# io3.net
KiCad netlist of a schematic drawn in EAGLE
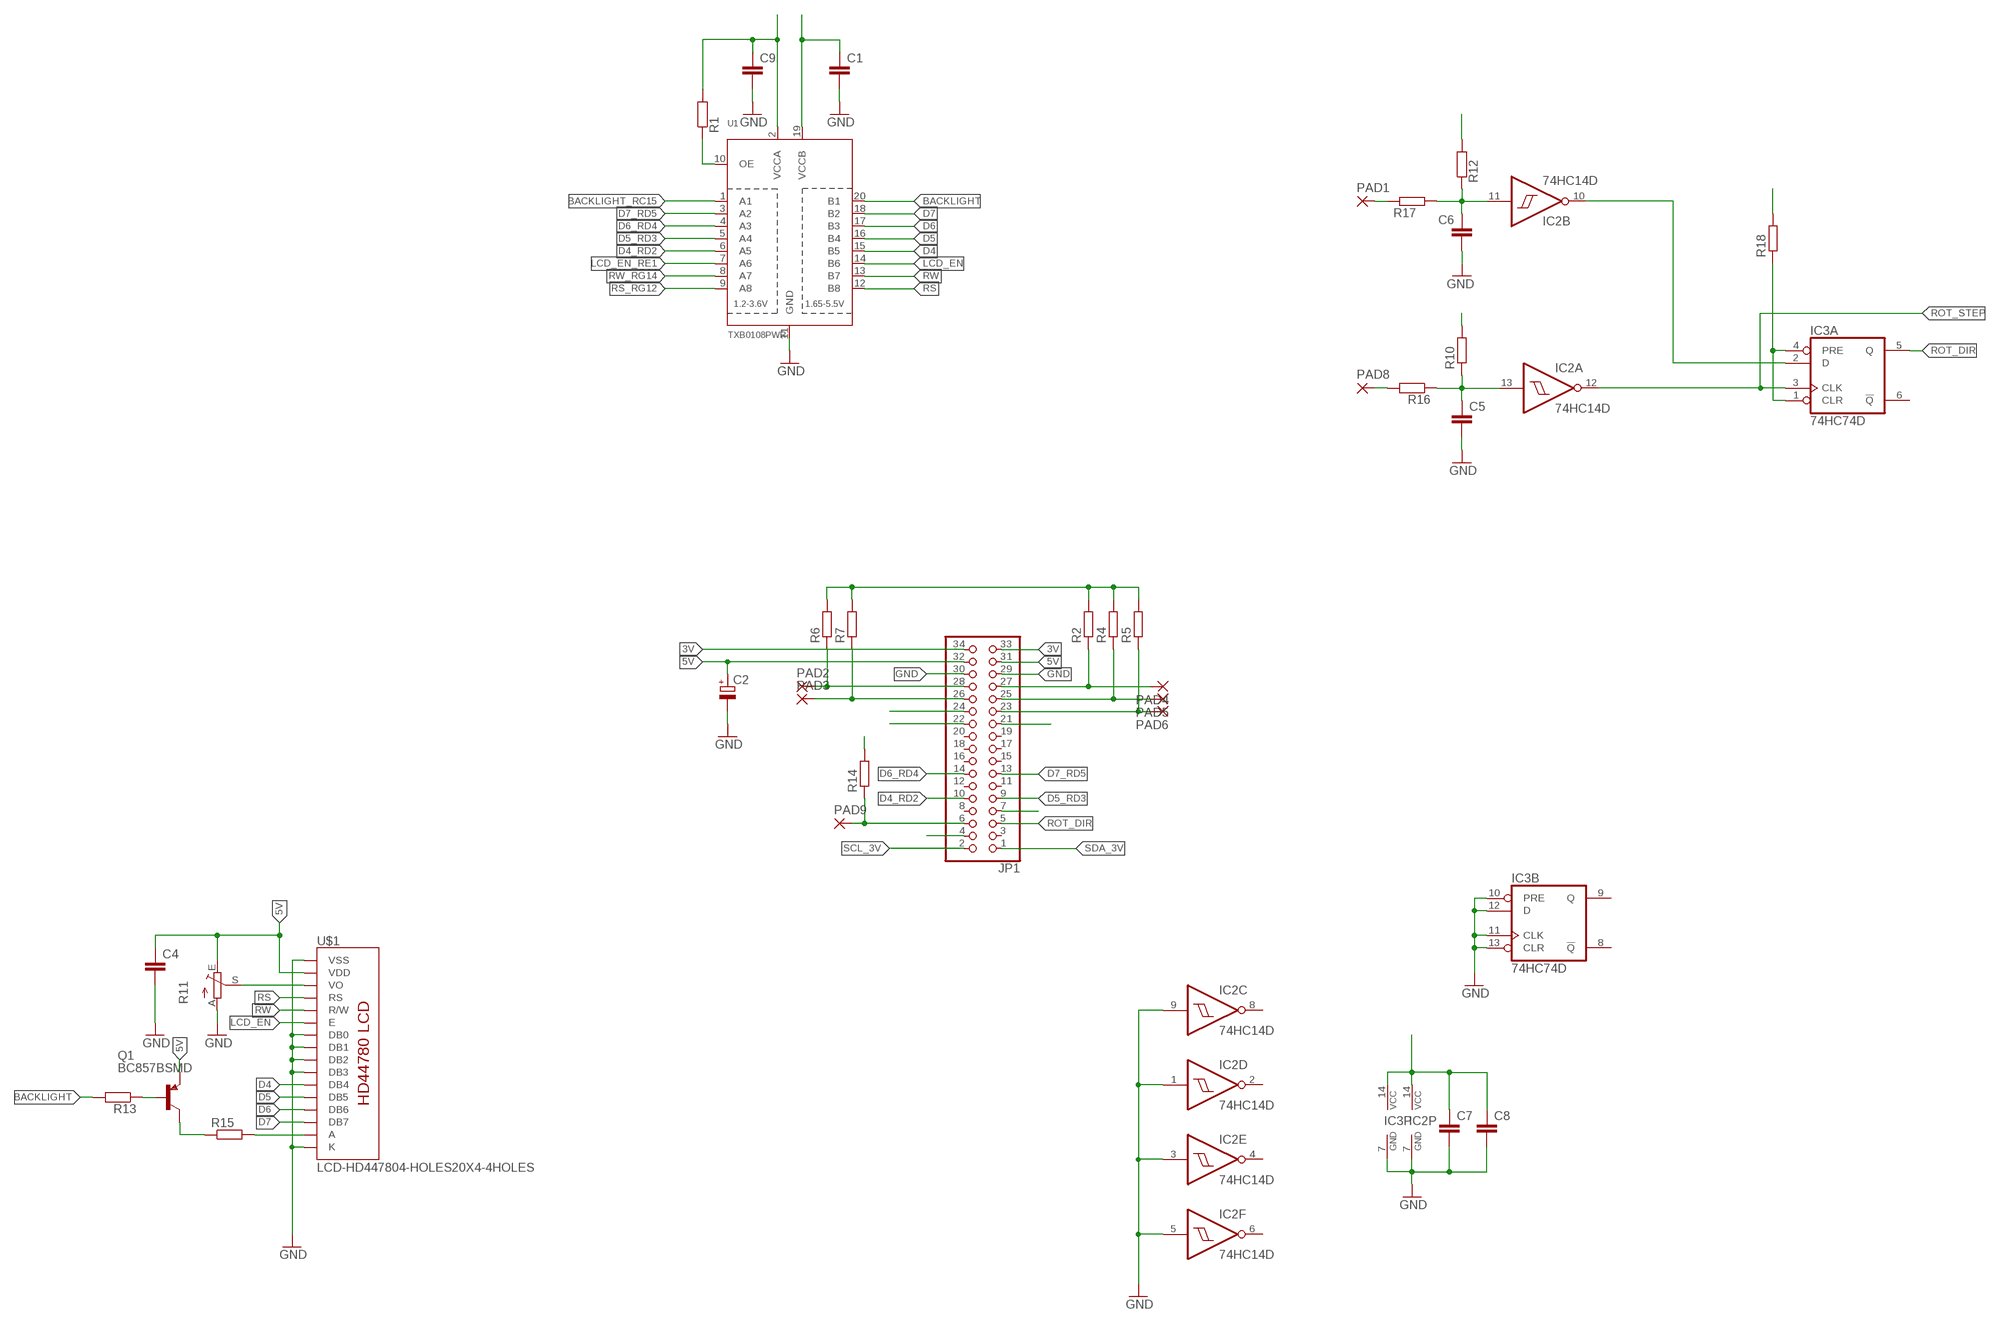
[diagram p0: schematic, sheet 1]

(export (version "E")
  (design (tool "Eeschema 10.0.6"))
  (components
    (comp (ref "C1")
      (value "C-EUC0603")
      (footprint "eagle-import:C0603")
      (libsource (lib "eagle-import") (part "C-EUC0603"))
    )
    (comp (ref "C2")
      (value "CPOL-EUSMCD")
      (footprint "eagle-import:SMC_D")
      (libsource (lib "eagle-import") (part "CPOL-EUSMCD"))
    )
    (comp (ref "C4")
      (value "C-EUC1206")
      (footprint "eagle-import:C1206")
      (libsource (lib "eagle-import") (part "C-EUC1206"))
    )
    (comp (ref "C5")
      (value "C-EUC0603")
      (footprint "eagle-import:C0603")
      (libsource (lib "eagle-import") (part "C-EUC0603"))
    )
    (comp (ref "C6")
      (value "C-EUC0603")
      (footprint "eagle-import:C0603")
      (libsource (lib "eagle-import") (part "C-EUC0603"))
    )
    (comp (ref "C7")
      (value "C-EUC0603")
      (footprint "eagle-import:C0603")
      (libsource (lib "eagle-import") (part "C-EUC0603"))
    )
    (comp (ref "C8")
      (value "C-EUC0603")
      (footprint "eagle-import:C0603")
      (libsource (lib "eagle-import") (part "C-EUC0603"))
    )
    (comp (ref "C9")
      (value "C-EUC0603")
      (footprint "eagle-import:C0603")
      (libsource (lib "eagle-import") (part "C-EUC0603"))
    )
    (comp (ref "IC2")
      (value "74HC14D")
      (footprint "eagle-import:SO14")
      (libsource (lib "eagle-import") (part "7414DHC"))
    )
    (comp (ref "IC3")
      (value "74HC74D")
      (footprint "eagle-import:SO14")
      (libsource (lib "eagle-import") (part "7474DHC"))
    )
    (comp (ref "JP1")
      (value "PINHD-2X17_2.54-SMD")
      (footprint "eagle-import:2X17SMD")
      (libsource (lib "eagle-import") (part "PINHD-2X17_2.54-SMD"))
    )
    (comp (ref "PAD1")
      (value "SMD2")
      (footprint "eagle-import:SMD1,27-2,54")
      (libsource (lib "eagle-import") (part "SMD2"))
    )
    (comp (ref "PAD2")
      (value "SMD2")
      (footprint "eagle-import:SMD1,27-2,54")
      (libsource (lib "eagle-import") (part "SMD2"))
    )
    (comp (ref "PAD3")
      (value "SMD2")
      (footprint "eagle-import:SMD1,27-2,54")
      (libsource (lib "eagle-import") (part "SMD2"))
    )
    (comp (ref "PAD4")
      (value "SMD2")
      (footprint "eagle-import:SMD1,27-2,54")
      (libsource (lib "eagle-import") (part "SMD2"))
    )
    (comp (ref "PAD5")
      (value "SMD2")
      (footprint "eagle-import:SMD1,27-2,54")
      (libsource (lib "eagle-import") (part "SMD2"))
    )
    (comp (ref "PAD6")
      (value "SMD2")
      (footprint "eagle-import:SMD1,27-2,54")
      (libsource (lib "eagle-import") (part "SMD2"))
    )
    (comp (ref "PAD8")
      (value "SMD2")
      (footprint "eagle-import:SMD1,27-2,54")
      (libsource (lib "eagle-import") (part "SMD2"))
    )
    (comp (ref "PAD9")
      (value "SMD2")
      (footprint "eagle-import:SMD1,27-2,54")
      (libsource (lib "eagle-import") (part "SMD2"))
    )
    (comp (ref "Q1")
      (value "BC857BSMD")
      (footprint "eagle-import:SOT23-BEC")
      (libsource (lib "eagle-import") (part "BC857SMDB"))
    )
    (comp (ref "R1")
      (value "R-EU_R0603")
      (footprint "eagle-import:R0603")
      (libsource (lib "eagle-import") (part "R-EU_R0603"))
    )
    (comp (ref "R2")
      (value "R-EU_0204/7")
      (footprint "eagle-import:0204_7")
      (libsource (lib "eagle-import") (part "R-EU_0204/7"))
    )
    (comp (ref "R4")
      (value "R-EU_0204/7")
      (footprint "eagle-import:0204_7")
      (libsource (lib "eagle-import") (part "R-EU_0204/7"))
    )
    (comp (ref "R5")
      (value "R-EU_0204/7")
      (footprint "eagle-import:0204_7")
      (libsource (lib "eagle-import") (part "R-EU_0204/7"))
    )
    (comp (ref "R6")
      (value "R-EU_0204/7")
      (footprint "eagle-import:0204_7")
      (libsource (lib "eagle-import") (part "R-EU_0204/7"))
    )
    (comp (ref "R7")
      (value "R-EU_0204/7")
      (footprint "eagle-import:0204_7")
      (libsource (lib "eagle-import") (part "R-EU_0204/7"))
    )
    (comp (ref "R10")
      (value "R-EU_0204/7")
      (footprint "eagle-import:0204_7")
      (libsource (lib "eagle-import") (part "R-EU_0204/7"))
    )
    (comp (ref "R11")
      (value "TRIM_EU-B25U")
      (footprint "eagle-import:B25U")
      (libsource (lib "eagle-import") (part "TRIM_EU-B25U"))
    )
    (comp (ref "R12")
      (value "R-EU_0204/7")
      (footprint "eagle-import:0204_7")
      (libsource (lib "eagle-import") (part "R-EU_0204/7"))
    )
    (comp (ref "R13")
      (value "R-EU_R0603")
      (footprint "eagle-import:R0603")
      (libsource (lib "eagle-import") (part "R-EU_R0603"))
    )
    (comp (ref "R14")
      (value "R-EU_0204/5")
      (footprint "eagle-import:0204_5")
      (libsource (lib "eagle-import") (part "R-EU_0204/5"))
    )
    (comp (ref "R15")
      (value "R-EU_R1206")
      (footprint "eagle-import:R1206")
      (libsource (lib "eagle-import") (part "R-EU_R1206"))
    )
    (comp (ref "R16")
      (value "R-EU_R0603")
      (footprint "eagle-import:R0603")
      (libsource (lib "eagle-import") (part "R-EU_R0603"))
    )
    (comp (ref "R17")
      (value "R-EU_R0603")
      (footprint "eagle-import:R0603")
      (libsource (lib "eagle-import") (part "R-EU_R0603"))
    )
    (comp (ref "R18")
      (value "R-EU_0204/7")
      (footprint "eagle-import:0204_7")
      (libsource (lib "eagle-import") (part "R-EU_0204/7"))
    )
    (comp (ref "U$1")
      (value "LCD-HD447804-HOLES20X4-4HOLES")
      (footprint "eagle-import:LCD-20X4-4HOLES")
      (libsource (lib "eagle-import") (part "LCD-HD4478020X4-4HOLES4-HOLES"))
    )
    (comp (ref "U1")
      (value "TXB0108PWR")
      (footprint "eagle-import:TSSOP20")
      (libsource (lib "eagle-import") (part "TXB0108PWR"))
    )
  )
  (nets
    (net (code "1") (name "3V") (class "Default")
      (node (ref "C7") (pin "1") (pinfunction "1_1") (pintype "passive"))
      (node (ref "C8") (pin "1") (pinfunction "1_1") (pintype "passive"))
      (node (ref "C9") (pin "1") (pinfunction "1_1") (pintype "passive"))
      (node (ref "IC2") (pin "14") (pinfunction "VCC_14") (pintype "power_in"))
      (node (ref "IC3") (pin "14") (pinfunction "VCC_14") (pintype "power_in"))
      (node (ref "JP1") (pin "33") (pinfunction "33_33") (pintype "passive"))
      (node (ref "JP1") (pin "34") (pinfunction "34_34") (pintype "passive"))
      (node (ref "R1") (pin "2") (pinfunction "2_2") (pintype "passive"))
      (node (ref "R10") (pin "2") (pinfunction "2_2") (pintype "passive"))
      (node (ref "R12") (pin "2") (pinfunction "2_2") (pintype "passive"))
      (node (ref "R14") (pin "2") (pinfunction "2_2") (pintype "passive"))
      (node (ref "R18") (pin "2") (pinfunction "2_2") (pintype "passive"))
      (node (ref "R2") (pin "2") (pinfunction "2_2") (pintype "passive"))
      (node (ref "R4") (pin "2") (pinfunction "2_2") (pintype "passive"))
      (node (ref "R5") (pin "2") (pinfunction "2_2") (pintype "passive"))
      (node (ref "R6") (pin "2") (pinfunction "2_2") (pintype "passive"))
      (node (ref "R7") (pin "2") (pinfunction "2_2") (pintype "passive"))
      (node (ref "U1") (pin "2") (pinfunction "VCCA_2") (pintype "bidirectional"))
    )
    (net (code "2") (name "5V") (class "Default")
      (node (ref "C1") (pin "1") (pinfunction "1_1") (pintype "passive"))
      (node (ref "C2") (pin "+") (pinfunction "+_+") (pintype "passive"))
      (node (ref "C4") (pin "1") (pinfunction "1_1") (pintype "passive"))
      (node (ref "JP1") (pin "31") (pinfunction "31_31") (pintype "passive"))
      (node (ref "JP1") (pin "32") (pinfunction "32_32") (pintype "passive"))
      (node (ref "Q1") (pin "E") (pinfunction "E_E") (pintype "passive"))
      (node (ref "R11") (pin "E") (pinfunction "E_E") (pintype "passive"))
      (node (ref "U$1") (pin "P$2") (pinfunction "VDD_P$2") (pintype "power_in"))
      (node (ref "U1") (pin "19") (pinfunction "VCCB_19") (pintype "bidirectional"))
    )
    (net (code "3") (name "BACKLIGHT") (class "Default")
      (node (ref "R13") (pin "2") (pinfunction "2_2") (pintype "passive"))
      (node (ref "U1") (pin "20") (pinfunction "B1_20") (pintype "bidirectional"))
    )
    (net (code "4") (name "BACKLIGHT_RC15") (class "Default")
      (node (ref "JP1") (pin "4") (pinfunction "4_4") (pintype "passive"))
      (node (ref "U1") (pin "1") (pinfunction "A1_1") (pintype "bidirectional"))
    )
    (net (code "5") (name "D4") (class "Default")
      (node (ref "U$1") (pin "P$11") (pinfunction "DB4_P$11") (pintype "bidirectional"))
      (node (ref "U1") (pin "15") (pinfunction "B5_15") (pintype "bidirectional"))
    )
    (net (code "6") (name "D4_RD2") (class "Default")
      (node (ref "JP1") (pin "10") (pinfunction "10_10") (pintype "passive"))
      (node (ref "U1") (pin "6") (pinfunction "A5_6") (pintype "bidirectional"))
    )
    (net (code "7") (name "D5") (class "Default")
      (node (ref "U$1") (pin "P$12") (pinfunction "DB5_P$12") (pintype "bidirectional"))
      (node (ref "U1") (pin "16") (pinfunction "B4_16") (pintype "bidirectional"))
    )
    (net (code "8") (name "D5_RD3") (class "Default")
      (node (ref "JP1") (pin "9") (pinfunction "9_9") (pintype "passive"))
      (node (ref "U1") (pin "5") (pinfunction "A4_5") (pintype "bidirectional"))
    )
    (net (code "9") (name "D6") (class "Default")
      (node (ref "U$1") (pin "P$13") (pinfunction "DB6_P$13") (pintype "bidirectional"))
      (node (ref "U1") (pin "17") (pinfunction "B3_17") (pintype "bidirectional"))
    )
    (net (code "10") (name "D6_RD4") (class "Default")
      (node (ref "JP1") (pin "14") (pinfunction "14_14") (pintype "passive"))
      (node (ref "U1") (pin "4") (pinfunction "A3_4") (pintype "bidirectional"))
    )
    (net (code "11") (name "D7") (class "Default")
      (node (ref "U$1") (pin "P$14") (pinfunction "DB7_P$14") (pintype "bidirectional"))
      (node (ref "U1") (pin "18") (pinfunction "B2_18") (pintype "bidirectional"))
    )
    (net (code "12") (name "D7_RD5") (class "Default")
      (node (ref "JP1") (pin "13") (pinfunction "13_13") (pintype "passive"))
      (node (ref "U1") (pin "3") (pinfunction "A2_3") (pintype "bidirectional"))
    )
    (net (code "13") (name "GND") (class "Default")
      (node (ref "C1") (pin "2") (pinfunction "2_2") (pintype "passive"))
      (node (ref "C2") (pin "-") (pinfunction "-_-") (pintype "passive"))
      (node (ref "C4") (pin "2") (pinfunction "2_2") (pintype "passive"))
      (node (ref "C5") (pin "2") (pinfunction "2_2") (pintype "passive"))
      (node (ref "C6") (pin "2") (pinfunction "2_2") (pintype "passive"))
      (node (ref "C7") (pin "2") (pinfunction "2_2") (pintype "passive"))
      (node (ref "C8") (pin "2") (pinfunction "2_2") (pintype "passive"))
      (node (ref "C9") (pin "2") (pinfunction "2_2") (pintype "passive"))
      (node (ref "IC2") (pin "1") (pinfunction "I_1") (pintype "input"))
      (node (ref "IC2") (pin "3") (pinfunction "I_3") (pintype "input"))
      (node (ref "IC2") (pin "5") (pinfunction "I_5") (pintype "input"))
      (node (ref "IC2") (pin "7") (pinfunction "GND_7") (pintype "power_in"))
      (node (ref "IC2") (pin "9") (pinfunction "I_9") (pintype "input"))
      (node (ref "IC3") (pin "10") (pinfunction "PRE_10") (pintype "input"))
      (node (ref "IC3") (pin "11") (pinfunction "CLK_11") (pintype "input"))
      (node (ref "IC3") (pin "12") (pinfunction "D_12") (pintype "input"))
      (node (ref "IC3") (pin "13") (pinfunction "CLR_13") (pintype "input"))
      (node (ref "IC3") (pin "7") (pinfunction "GND_7") (pintype "power_in"))
      (node (ref "JP1") (pin "29") (pinfunction "29_29") (pintype "passive"))
      (node (ref "JP1") (pin "30") (pinfunction "30_30") (pintype "passive"))
      (node (ref "R11") (pin "A") (pinfunction "A_A") (pintype "passive"))
      (node (ref "U$1") (pin "P$1") (pinfunction "VSS_P$1") (pintype "power_in"))
      (node (ref "U$1") (pin "P$10") (pinfunction "DB3_P$10") (pintype "bidirectional"))
      (node (ref "U$1") (pin "P$16") (pinfunction "K_P$16") (pintype "power_in"))
      (node (ref "U$1") (pin "P$7") (pinfunction "DB0_P$7") (pintype "bidirectional"))
      (node (ref "U$1") (pin "P$8") (pinfunction "DB1_P$8") (pintype "bidirectional"))
      (node (ref "U$1") (pin "P$9") (pinfunction "DB2_P$9") (pintype "bidirectional"))
      (node (ref "U1") (pin "11") (pinfunction "GND_11") (pintype "bidirectional"))
    )
    (net (code "14") (name "LCD_EN") (class "Default")
      (node (ref "U$1") (pin "P$6") (pinfunction "E_P$6") (pintype "input"))
      (node (ref "U1") (pin "14") (pinfunction "B6_14") (pintype "bidirectional"))
    )
    (net (code "15") (name "LCD_EN_RE1") (class "Default")
      (node (ref "JP1") (pin "22") (pinfunction "22_22") (pintype "passive"))
      (node (ref "U1") (pin "7") (pinfunction "A6_7") (pintype "bidirectional"))
    )
    (net (code "16") (name "Net-(IC2A-I)") (class "Default")
      (node (ref "C5") (pin "1") (pinfunction "1_1") (pintype "passive"))
      (node (ref "IC2") (pin "13") (pinfunction "I_13") (pintype "input"))
      (node (ref "R10") (pin "1") (pinfunction "1_1") (pintype "passive"))
      (node (ref "R16") (pin "1") (pinfunction "1_1") (pintype "passive"))
    )
    (net (code "17") (name "Net-(IC2B-I)") (class "Default")
      (node (ref "C6") (pin "1") (pinfunction "1_1") (pintype "passive"))
      (node (ref "IC2") (pin "11") (pinfunction "I_11") (pintype "input"))
      (node (ref "R12") (pin "1") (pinfunction "1_1") (pintype "passive"))
      (node (ref "R17") (pin "2") (pinfunction "2_2") (pintype "passive"))
    )
    (net (code "18") (name "Net-(IC2B-O)") (class "Default")
      (node (ref "IC2") (pin "10") (pinfunction "O_10") (pintype "output"))
      (node (ref "IC3") (pin "2") (pinfunction "D_2") (pintype "input"))
    )
    (net (code "19") (name "Net-(IC3A-CLR)") (class "Default")
      (node (ref "IC3") (pin "1") (pinfunction "CLR_1") (pintype "input"))
      (node (ref "IC3") (pin "4") (pinfunction "PRE_4") (pintype "input"))
      (node (ref "R18") (pin "1") (pinfunction "1_1") (pintype "passive"))
    )
    (net (code "20") (name "Net-(PAD1-P)") (class "Default")
      (node (ref "PAD1") (pin "1") (pinfunction "P_1") (pintype "passive"))
      (node (ref "R17") (pin "1") (pinfunction "1_1") (pintype "passive"))
    )
    (net (code "21") (name "Net-(PAD2-P)") (class "Default")
      (node (ref "JP1") (pin "28") (pinfunction "28_28") (pintype "passive"))
      (node (ref "PAD2") (pin "1") (pinfunction "P_1") (pintype "passive"))
      (node (ref "R6") (pin "1") (pinfunction "1_1") (pintype "passive"))
    )
    (net (code "22") (name "Net-(PAD3-P)") (class "Default")
      (node (ref "JP1") (pin "26") (pinfunction "26_26") (pintype "passive"))
      (node (ref "PAD3") (pin "1") (pinfunction "P_1") (pintype "passive"))
      (node (ref "R7") (pin "1") (pinfunction "1_1") (pintype "passive"))
    )
    (net (code "23") (name "Net-(PAD4-P)") (class "Default")
      (node (ref "JP1") (pin "27") (pinfunction "27_27") (pintype "passive"))
      (node (ref "PAD4") (pin "1") (pinfunction "P_1") (pintype "passive"))
      (node (ref "R2") (pin "1") (pinfunction "1_1") (pintype "passive"))
    )
    (net (code "24") (name "Net-(PAD5-P)") (class "Default")
      (node (ref "JP1") (pin "25") (pinfunction "25_25") (pintype "passive"))
      (node (ref "PAD5") (pin "1") (pinfunction "P_1") (pintype "passive"))
      (node (ref "R4") (pin "1") (pinfunction "1_1") (pintype "passive"))
    )
    (net (code "25") (name "Net-(PAD6-P)") (class "Default")
      (node (ref "JP1") (pin "23") (pinfunction "23_23") (pintype "passive"))
      (node (ref "PAD6") (pin "1") (pinfunction "P_1") (pintype "passive"))
      (node (ref "R5") (pin "1") (pinfunction "1_1") (pintype "passive"))
    )
    (net (code "26") (name "Net-(PAD8-P)") (class "Default")
      (node (ref "PAD8") (pin "1") (pinfunction "P_1") (pintype "passive"))
      (node (ref "R16") (pin "2") (pinfunction "2_2") (pintype "passive"))
    )
    (net (code "27") (name "Net-(PAD9-P)") (class "Default")
      (node (ref "JP1") (pin "6") (pinfunction "6_6") (pintype "passive"))
      (node (ref "PAD9") (pin "1") (pinfunction "P_1") (pintype "passive"))
      (node (ref "R14") (pin "1") (pinfunction "1_1") (pintype "passive"))
    )
    (net (code "28") (name "Net-(Q1-PadB)") (class "Default")
      (node (ref "Q1") (pin "B") (pinfunction "B_B") (pintype "passive"))
      (node (ref "R13") (pin "1") (pinfunction "1_1") (pintype "passive"))
    )
    (net (code "29") (name "Net-(Q1-PadC)") (class "Default")
      (node (ref "Q1") (pin "C") (pinfunction "C_C") (pintype "passive"))
      (node (ref "R15") (pin "1") (pinfunction "1_1") (pintype "passive"))
    )
    (net (code "30") (name "Net-(U$1-A)") (class "Default")
      (node (ref "R15") (pin "2") (pinfunction "2_2") (pintype "passive"))
      (node (ref "U$1") (pin "P$15") (pinfunction "A_P$15") (pintype "power_in"))
    )
    (net (code "31") (name "Net-(U$1-VO)") (class "Default")
      (node (ref "R11") (pin "S") (pinfunction "S_S") (pintype "passive"))
      (node (ref "U$1") (pin "P$3") (pinfunction "VO_P$3") (pintype "bidirectional"))
    )
    (net (code "32") (name "Net-(U1-OE)") (class "Default")
      (node (ref "R1") (pin "1") (pinfunction "1_1") (pintype "passive"))
      (node (ref "U1") (pin "10") (pinfunction "OE_10") (pintype "bidirectional"))
    )
    (net (code "33") (name "ROT_DIR") (class "Default")
      (node (ref "IC3") (pin "5") (pinfunction "Q_5") (pintype "output"))
      (node (ref "JP1") (pin "5") (pinfunction "5_5") (pintype "passive"))
    )
    (net (code "34") (name "ROT_STEP") (class "Default")
      (node (ref "IC2") (pin "12") (pinfunction "O_12") (pintype "output"))
      (node (ref "IC3") (pin "3") (pinfunction "CLK_3") (pintype "input"))
      (node (ref "JP1") (pin "7") (pinfunction "7_7") (pintype "passive"))
    )
    (net (code "35") (name "RS") (class "Default")
      (node (ref "U$1") (pin "P$4") (pinfunction "RS_P$4") (pintype "input"))
      (node (ref "U1") (pin "12") (pinfunction "B8_12") (pintype "bidirectional"))
    )
    (net (code "36") (name "RS_RG12") (class "Default")
      (node (ref "JP1") (pin "24") (pinfunction "24_24") (pintype "passive"))
      (node (ref "U1") (pin "9") (pinfunction "A8_9") (pintype "bidirectional"))
    )
    (net (code "37") (name "RW") (class "Default")
      (node (ref "U$1") (pin "P$5") (pinfunction "R/W_P$5") (pintype "input"))
      (node (ref "U1") (pin "13") (pinfunction "B7_13") (pintype "bidirectional"))
    )
    (net (code "38") (name "RW_RG14") (class "Default")
      (node (ref "JP1") (pin "21") (pinfunction "21_21") (pintype "passive"))
      (node (ref "U1") (pin "8") (pinfunction "A7_8") (pintype "bidirectional"))
    )
    (net (code "39") (name "SCL_3V") (class "Default")
      (node (ref "JP1") (pin "2") (pinfunction "2_2") (pintype "passive"))
    )
    (net (code "40") (name "SDA_3V") (class "Default")
      (node (ref "JP1") (pin "1") (pinfunction "1_1") (pintype "passive"))
    )
    (net (code "41") (name "unconnected-(IC2C-O-Pad8)") (class "Default")
      (node (ref "IC2") (pin "8") (pinfunction "O_8") (pintype "output"))
    )
    (net (code "42") (name "unconnected-(IC2D-O-Pad2)") (class "Default")
      (node (ref "IC2") (pin "2") (pinfunction "O_2") (pintype "output"))
    )
    (net (code "43") (name "unconnected-(IC2E-O-Pad4)") (class "Default")
      (node (ref "IC2") (pin "4") (pinfunction "O_4") (pintype "output"))
    )
    (net (code "44") (name "unconnected-(IC2F-O-Pad6)") (class "Default")
      (node (ref "IC2") (pin "6") (pinfunction "O_6") (pintype "output"))
    )
    (net (code "45") (name "unconnected-(IC3A-~{Q}-Pad6)") (class "Default")
      (node (ref "IC3") (pin "6") (pinfunction "~{Q}_6") (pintype "output"))
    )
    (net (code "46") (name "unconnected-(IC3B-Q-Pad9)") (class "Default")
      (node (ref "IC3") (pin "9") (pinfunction "Q_9") (pintype "output"))
    )
    (net (code "47") (name "unconnected-(IC3B-~{Q}-Pad8)") (class "Default")
      (node (ref "IC3") (pin "8") (pinfunction "~{Q}_8") (pintype "output"))
    )
    (net (code "48") (name "unconnected-(JP1-Pad3)") (class "Default")
      (node (ref "JP1") (pin "3") (pinfunction "3_3") (pintype "passive"))
    )
    (net (code "49") (name "unconnected-(JP1-Pad8)") (class "Default")
      (node (ref "JP1") (pin "8") (pinfunction "8_8") (pintype "passive"))
    )
    (net (code "50") (name "unconnected-(JP1-Pad11)") (class "Default")
      (node (ref "JP1") (pin "11") (pinfunction "11_11") (pintype "passive"))
    )
    (net (code "51") (name "unconnected-(JP1-Pad12)") (class "Default")
      (node (ref "JP1") (pin "12") (pinfunction "12_12") (pintype "passive"))
    )
    (net (code "52") (name "unconnected-(JP1-Pad15)") (class "Default")
      (node (ref "JP1") (pin "15") (pinfunction "15_15") (pintype "passive"))
    )
    (net (code "53") (name "unconnected-(JP1-Pad16)") (class "Default")
      (node (ref "JP1") (pin "16") (pinfunction "16_16") (pintype "passive"))
    )
    (net (code "54") (name "unconnected-(JP1-Pad17)") (class "Default")
      (node (ref "JP1") (pin "17") (pinfunction "17_17") (pintype "passive"))
    )
    (net (code "55") (name "unconnected-(JP1-Pad18)") (class "Default")
      (node (ref "JP1") (pin "18") (pinfunction "18_18") (pintype "passive"))
    )
    (net (code "56") (name "unconnected-(JP1-Pad19)") (class "Default")
      (node (ref "JP1") (pin "19") (pinfunction "19_19") (pintype "passive"))
    )
    (net (code "57") (name "unconnected-(JP1-Pad20)") (class "Default")
      (node (ref "JP1") (pin "20") (pinfunction "20_20") (pintype "passive"))
    )
  )
)
